# Sheet1.net
KiCad netlist of a schematic drawn in Altium Designer
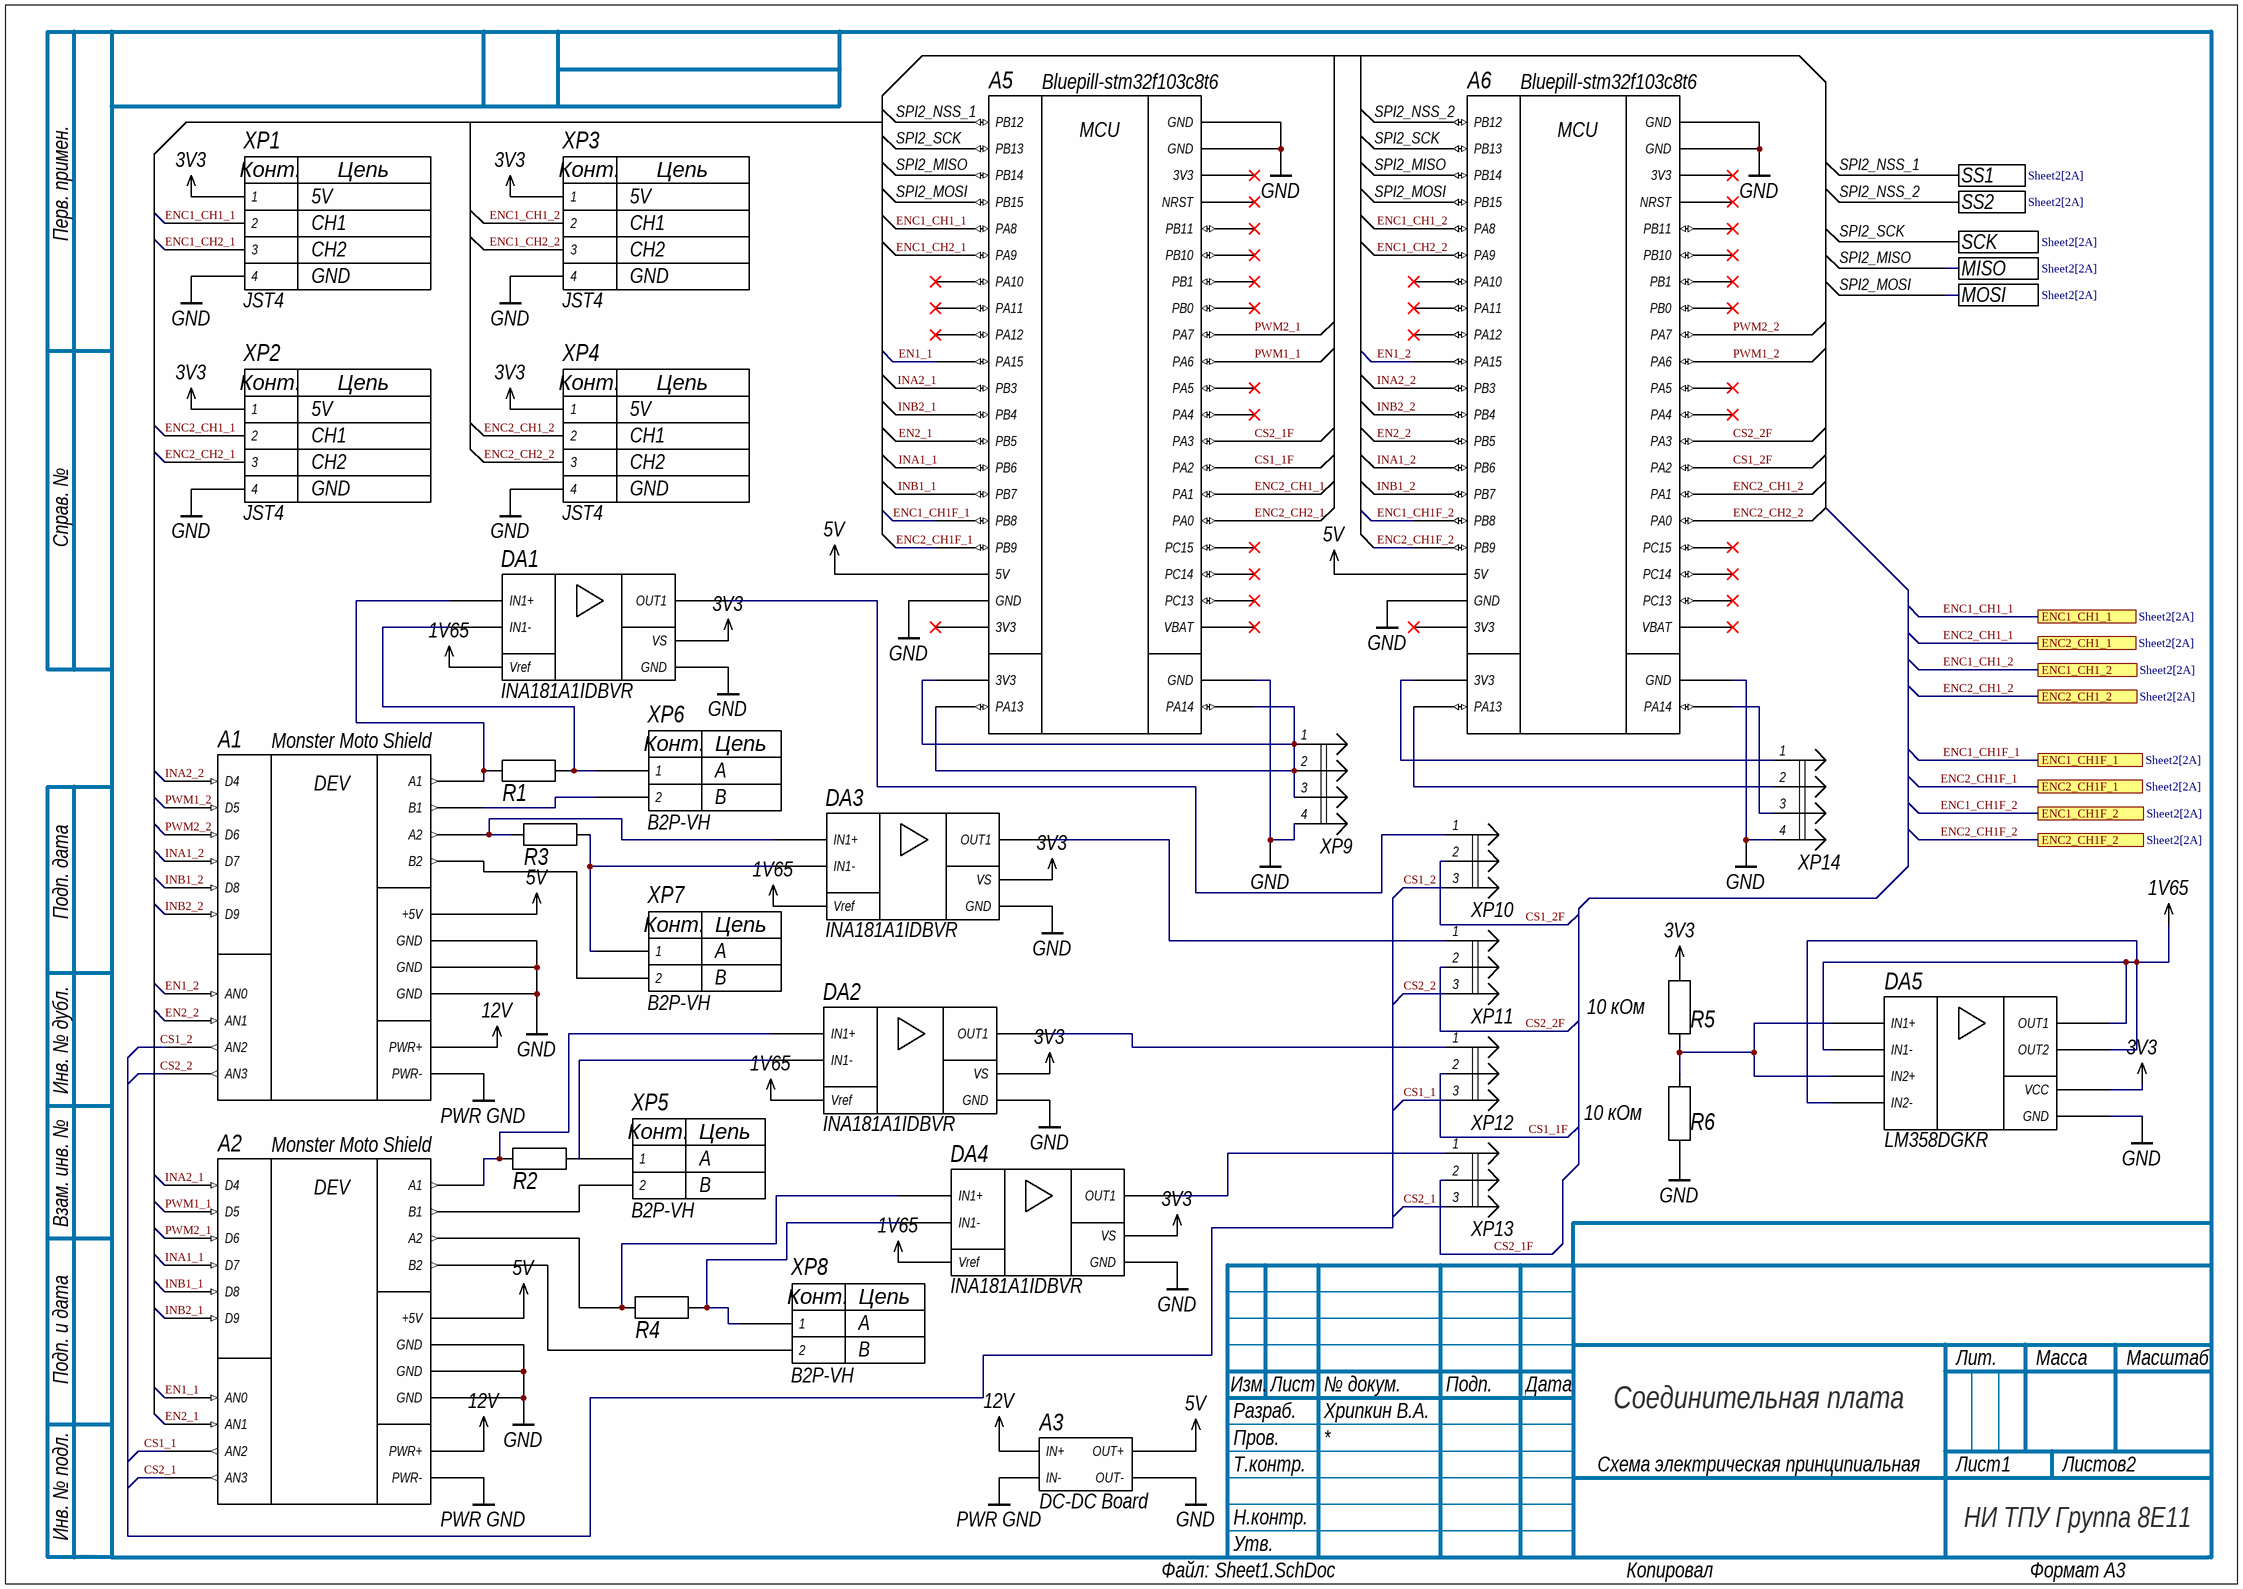
[diagram p0: Sheet1.SchDoc]

(export (version "E")
  (design (tool "Eeschema 10.0.6"))
  (components
    (comp (ref "A1")
      (value "Monster Moto Shield")
      (footprint "Monster Moto Shield")
      (libsource (lib "Schlib1") (part "MonsterMotoShield"))
    )
    (comp (ref "A2")
      (value "Monster Moto Shield")
      (footprint "Monster Moto Shield")
      (libsource (lib "Schlib1") (part "MonsterMotoShield"))
    )
    (comp (ref "A3")
      (value "DC-DC Board")
      (footprint "DC-DC Board")
      (description "Преобразователь напряжений 12-5В")
      (libsource (lib "Schlib1") (part "DC-DC"))
    )
    (comp (ref "A5")
      (value "Bluepill-stm32f103c8t6")
      (footprint "BluePill")
      (description "Отладочная плата на основе микроконтроллера stm32f103c8t6")
      (libsource (lib "Schlib1") (part "BluePill"))
    )
    (comp (ref "A6")
      (value "Bluepill-stm32f103c8t6")
      (footprint "BluePill")
      (description "Отладочная плата на основе микроконтроллера stm32f103c8t6")
      (libsource (lib "Schlib1") (part "BluePill"))
    )
    (comp (ref "DA1")
      (value "INA181A1IDBVR")
      (footprint "SOT236")
      (description "Усилители операционные, дифференциальные, инструментальные, Gain 20, SOT236")
      (libsource (lib "Schlib1") (part "INA181A1IDBVR"))
    )
    (comp (ref "DA2")
      (value "INA181A1IDBVR")
      (footprint "SOT236")
      (description "Усилители операционные, дифференциальные, инструментальные, Gain 20, SOT236")
      (libsource (lib "Schlib1") (part "INA181A1IDBVR"))
    )
    (comp (ref "DA3")
      (value "INA181A1IDBVR")
      (footprint "SOT236")
      (description "Усилители операционные, дифференциальные, инструментальные, Gain 20, SOT236")
      (libsource (lib "Schlib1") (part "INA181A1IDBVR"))
    )
    (comp (ref "DA4")
      (value "INA181A1IDBVR")
      (footprint "SOT236")
      (description "Усилители операционные, дифференциальные, инструментальные, Gain 20, SOT236")
      (libsource (lib "Schlib1") (part "INA181A1IDBVR"))
    )
    (comp (ref "DA5")
      (value "LM358DGKR")
      (footprint "VSSOP-8")
      (description "Операционный усилитель, Двойной, 700 кГц, 0.3 В/мкс, 3В до 32В, ± 1.5В до ± 16В, [VSSOP-8]")
      (libsource (lib "Schlib1") (part "LM358DGKR"))
    )
    (comp (ref "R1")
      (value "ва")
      (footprint "R1210")
      (description "Резистор постоянный")
      (libsource (lib "Schlib1") (part "Resisitor"))
    )
    (comp (ref "R2")
      (value "ва")
      (footprint "R1210")
      (description "Резистор постоянный")
      (libsource (lib "Schlib1") (part "Resisitor"))
    )
    (comp (ref "R3")
      (value "ва")
      (footprint "R1210")
      (description "Резистор постоянный")
      (libsource (lib "Schlib1") (part "Resisitor"))
    )
    (comp (ref "R4")
      (value "ва")
      (footprint "R1210")
      (description "Резистор постоянный")
      (libsource (lib "Schlib1") (part "Resisitor"))
    )
    (comp (ref "R5")
      (value "ва")
      (footprint "R0603")
      (description "Резистор постоянный")
      (libsource (lib "Schlib1") (part "R1_POSTOYANNYJ_W0.5"))
    )
    (comp (ref "R6")
      (value "ва")
      (footprint "R0603")
      (description "Резистор постоянный")
      (libsource (lib "Schlib1") (part "R1_POSTOYANNYJ_W0.5"))
    )
    (comp (ref "XP1") (value "JST4") (footprint "JST 4pin") (libsource (lib "Schlib1") (part "JST4")))
    (comp (ref "XP2") (value "JST4") (footprint "JST 4pin") (libsource (lib "Schlib1") (part "JST4")))
    (comp (ref "XP3") (value "JST4") (footprint "JST 4pin") (libsource (lib "Schlib1") (part "JST4")))
    (comp (ref "XP4") (value "JST4") (footprint "JST 4pin") (libsource (lib "Schlib1") (part "JST4")))
    (comp (ref "XP5")
      (value "B2P-VH")
      (footprint "B2P-VH")
      (description "JST VH(B2P-VH)")
      (libsource (lib "Schlib1") (part "JST VH(B2P-VH)"))
    )
    (comp (ref "XP6")
      (value "B2P-VH")
      (footprint "B2P-VH")
      (description "JST VH(B2P-VH)")
      (libsource (lib "Schlib1") (part "JST VH(B2P-VH)"))
    )
    (comp (ref "XP7")
      (value "B2P-VH")
      (footprint "B2P-VH")
      (description "JST VH(B2P-VH)")
      (libsource (lib "Schlib1") (part "JST VH(B2P-VH)"))
    )
    (comp (ref "XP8")
      (value "B2P-VH")
      (footprint "B2P-VH")
      (description "JST VH(B2P-VH)")
      (libsource (lib "Schlib1") (part "JST VH(B2P-VH)"))
    )
    (comp (ref "XP9")
      (value "~")
      (footprint "PLS-4")
      (description "PLS4")
      (libsource (lib "Schlib1") (part "Connector-4"))
    )
    (comp (ref "XP10")
      (value "~")
      (footprint "PLS-3")
      (description "PLS3")
      (libsource (lib "Schlib1") (part "Connector-3"))
    )
    (comp (ref "XP11")
      (value "~")
      (footprint "PLS-3")
      (description "PLS3")
      (libsource (lib "Schlib1") (part "Connector-3"))
    )
    (comp (ref "XP12")
      (value "~")
      (footprint "PLS-3")
      (description "PLS3")
      (libsource (lib "Schlib1") (part "Connector-3"))
    )
    (comp (ref "XP13")
      (value "~")
      (footprint "PLS-3")
      (description "PLS3")
      (libsource (lib "Schlib1") (part "Connector-3"))
    )
    (comp (ref "XP14")
      (value "~")
      (footprint "PLS-4")
      (description "PLS4")
      (libsource (lib "Schlib1") (part "Connector-4"))
    )
  )
  (nets
    (net (code "1") (name "/CS1_1") (class "Default")
      (node (ref "A2") (pin "3") (pinfunction "AN2_3") (pintype "output"))
      (node (ref "XP12") (pin "3") (pinfunction "3_3") (pintype "passive"))
    )
    (net (code "2") (name "/CS1_1F") (class "Default")
      (node (ref "A5") (pin "34") (pinfunction "PA2_34") (pintype "bidirectional"))
      (node (ref "XP12") (pin "2") (pinfunction "2_2") (pintype "passive"))
    )
    (net (code "3") (name "/CS1_2") (class "Default")
      (node (ref "A1") (pin "3") (pinfunction "AN2_3") (pintype "output"))
      (node (ref "XP10") (pin "3") (pinfunction "3_3") (pintype "passive"))
    )
    (net (code "4") (name "/CS1_2F") (class "Default")
      (node (ref "A6") (pin "34") (pinfunction "PA2_34") (pintype "bidirectional"))
      (node (ref "XP10") (pin "2") (pinfunction "2_2") (pintype "passive"))
    )
    (net (code "5") (name "/CS2_1") (class "Default")
      (node (ref "A2") (pin "4") (pinfunction "AN3_4") (pintype "output"))
      (node (ref "XP13") (pin "3") (pinfunction "3_3") (pintype "passive"))
    )
    (net (code "6") (name "/CS2_1F") (class "Default")
      (node (ref "A5") (pin "33") (pinfunction "PA3_33") (pintype "bidirectional"))
      (node (ref "XP13") (pin "2") (pinfunction "2_2") (pintype "passive"))
    )
    (net (code "7") (name "/CS2_2") (class "Default")
      (node (ref "A1") (pin "4") (pinfunction "AN3_4") (pintype "output"))
      (node (ref "XP11") (pin "3") (pinfunction "3_3") (pintype "passive"))
    )
    (net (code "8") (name "/CS2_2F") (class "Default")
      (node (ref "A6") (pin "33") (pinfunction "PA3_33") (pintype "bidirectional"))
      (node (ref "XP11") (pin "2") (pinfunction "2_2") (pintype "passive"))
    )
    (net (code "9") (name "/EN1_1") (class "Default")
      (node (ref "A2") (pin "1") (pinfunction "AN0_1") (pintype "input"))
      (node (ref "A5") (pin "10") (pinfunction "PA15_10") (pintype "bidirectional"))
    )
    (net (code "10") (name "/EN1_2") (class "Default")
      (node (ref "A1") (pin "1") (pinfunction "AN0_1") (pintype "input"))
      (node (ref "A6") (pin "10") (pinfunction "PA15_10") (pintype "bidirectional"))
    )
    (net (code "11") (name "/EN2_1") (class "Default")
      (node (ref "A2") (pin "2") (pinfunction "AN1_2") (pintype "input"))
      (node (ref "A5") (pin "13") (pinfunction "PB5_13") (pintype "bidirectional"))
    )
    (net (code "12") (name "/EN2_2") (class "Default")
      (node (ref "A1") (pin "2") (pinfunction "AN1_2") (pintype "input"))
      (node (ref "A6") (pin "13") (pinfunction "PB5_13") (pintype "bidirectional"))
    )
    (net (code "13") (name "/ENC1_CH1F_1") (class "Default")
      (node (ref "A5") (pin "16") (pinfunction "PB8_16") (pintype "bidirectional"))
    )
    (net (code "14") (name "/ENC1_CH1F_2") (class "Default")
      (node (ref "A6") (pin "16") (pinfunction "PB8_16") (pintype "bidirectional"))
    )
    (net (code "15") (name "/ENC1_CH1_1") (class "Default")
      (node (ref "A5") (pin "5") (pinfunction "PA8_5") (pintype "bidirectional"))
      (node (ref "XP1") (pin "2") (pinfunction "2_2") (pintype "passive"))
    )
    (net (code "16") (name "/ENC1_CH1_2") (class "Default")
      (node (ref "A6") (pin "5") (pinfunction "PA8_5") (pintype "bidirectional"))
      (node (ref "XP3") (pin "2") (pinfunction "2_2") (pintype "passive"))
    )
    (net (code "17") (name "/ENC1_CH2_1") (class "Default")
      (node (ref "A5") (pin "6") (pinfunction "PA9_6") (pintype "bidirectional"))
      (node (ref "XP1") (pin "3") (pinfunction "3_3") (pintype "passive"))
    )
    (net (code "18") (name "/ENC1_CH2_2") (class "Default")
      (node (ref "A6") (pin "6") (pinfunction "PA9_6") (pintype "bidirectional"))
      (node (ref "XP3") (pin "3") (pinfunction "3_3") (pintype "passive"))
    )
    (net (code "19") (name "/ENC2_CH1F_1") (class "Default")
      (node (ref "A5") (pin "17") (pinfunction "PB9_17") (pintype "bidirectional"))
    )
    (net (code "20") (name "/ENC2_CH1F_2") (class "Default")
      (node (ref "A6") (pin "17") (pinfunction "PB9_17") (pintype "bidirectional"))
    )
    (net (code "21") (name "/ENC2_CH1_1") (class "Default")
      (node (ref "A5") (pin "35") (pinfunction "PA1_35") (pintype "bidirectional"))
      (node (ref "XP2") (pin "2") (pinfunction "2_2") (pintype "passive"))
    )
    (net (code "22") (name "/ENC2_CH1_2") (class "Default")
      (node (ref "A6") (pin "35") (pinfunction "PA1_35") (pintype "bidirectional"))
      (node (ref "XP4") (pin "2") (pinfunction "2_2") (pintype "passive"))
    )
    (net (code "23") (name "/ENC2_CH2_1") (class "Default")
      (node (ref "A5") (pin "36") (pinfunction "PA0_36") (pintype "bidirectional"))
      (node (ref "XP2") (pin "3") (pinfunction "3_3") (pintype "passive"))
    )
    (net (code "24") (name "/ENC2_CH2_2") (class "Default")
      (node (ref "A6") (pin "36") (pinfunction "PA0_36") (pintype "bidirectional"))
      (node (ref "XP4") (pin "3") (pinfunction "3_3") (pintype "passive"))
    )
    (net (code "25") (name "/INA1_1") (class "Default")
      (node (ref "A2") (pin "8") (pinfunction "D7_8") (pintype "input"))
      (node (ref "A5") (pin "14") (pinfunction "PB6_14") (pintype "bidirectional"))
    )
    (net (code "26") (name "/INA1_2") (class "Default")
      (node (ref "A1") (pin "8") (pinfunction "D7_8") (pintype "input"))
      (node (ref "A6") (pin "14") (pinfunction "PB6_14") (pintype "bidirectional"))
    )
    (net (code "27") (name "/INA2_1") (class "Default")
      (node (ref "A2") (pin "5") (pinfunction "D4_5") (pintype "input"))
      (node (ref "A5") (pin "11") (pinfunction "PB3_11") (pintype "bidirectional"))
    )
    (net (code "28") (name "/INA2_2") (class "Default")
      (node (ref "A1") (pin "5") (pinfunction "D4_5") (pintype "input"))
      (node (ref "A6") (pin "11") (pinfunction "PB3_11") (pintype "bidirectional"))
    )
    (net (code "29") (name "/INB1_1") (class "Default")
      (node (ref "A2") (pin "9") (pinfunction "D8_9") (pintype "input"))
      (node (ref "A5") (pin "15") (pinfunction "PB7_15") (pintype "bidirectional"))
    )
    (net (code "30") (name "/INB1_2") (class "Default")
      (node (ref "A1") (pin "9") (pinfunction "D8_9") (pintype "input"))
      (node (ref "A6") (pin "15") (pinfunction "PB7_15") (pintype "bidirectional"))
    )
    (net (code "31") (name "/INB2_1") (class "Default")
      (node (ref "A2") (pin "10") (pinfunction "D9_10") (pintype "input"))
      (node (ref "A5") (pin "12") (pinfunction "PB4_12") (pintype "bidirectional"))
    )
    (net (code "32") (name "/INB2_2") (class "Default")
      (node (ref "A1") (pin "10") (pinfunction "D9_10") (pintype "input"))
      (node (ref "A6") (pin "12") (pinfunction "PB4_12") (pintype "bidirectional"))
    )
    (net (code "33") (name "/PWM1_1") (class "Default")
      (node (ref "A2") (pin "6") (pinfunction "D5_6") (pintype "input"))
      (node (ref "A5") (pin "30") (pinfunction "PA6_30") (pintype "bidirectional"))
    )
    (net (code "34") (name "/PWM1_2") (class "Default")
      (node (ref "A1") (pin "6") (pinfunction "D5_6") (pintype "input"))
      (node (ref "A6") (pin "30") (pinfunction "PA6_30") (pintype "bidirectional"))
    )
    (net (code "35") (name "/PWM2_1") (class "Default")
      (node (ref "A2") (pin "7") (pinfunction "D6_7") (pintype "input"))
      (node (ref "A5") (pin "29") (pinfunction "PA7_29") (pintype "bidirectional"))
    )
    (net (code "36") (name "/PWM2_2") (class "Default")
      (node (ref "A1") (pin "7") (pinfunction "D6_7") (pintype "input"))
      (node (ref "A6") (pin "29") (pinfunction "PA7_29") (pintype "bidirectional"))
    )
    (net (code "37") (name "/SPI2_MISO") (class "Default")
      (node (ref "A5") (pin "3") (pinfunction "PB14_3") (pintype "bidirectional"))
      (node (ref "A6") (pin "3") (pinfunction "PB14_3") (pintype "bidirectional"))
    )
    (net (code "38") (name "/SPI2_MOSI") (class "Default")
      (node (ref "A5") (pin "4") (pinfunction "PB15_4") (pintype "bidirectional"))
      (node (ref "A6") (pin "4") (pinfunction "PB15_4") (pintype "bidirectional"))
    )
    (net (code "39") (name "/SPI2_NSS_1") (class "Default")
      (node (ref "A5") (pin "1") (pinfunction "PB12_1") (pintype "bidirectional"))
    )
    (net (code "40") (name "/SPI2_NSS_2") (class "Default")
      (node (ref "A6") (pin "1") (pinfunction "PB12_1") (pintype "bidirectional"))
    )
    (net (code "41") (name "/SPI2_SCK") (class "Default")
      (node (ref "A5") (pin "2") (pinfunction "PB13_2") (pintype "bidirectional"))
      (node (ref "A6") (pin "2") (pinfunction "PB13_2") (pintype "bidirectional"))
    )
    (net (code "42") (name "1V65") (class "Default")
      (node (ref "DA1") (pin "1") (pinfunction "Vref_1") (pintype "passive"))
      (node (ref "DA2") (pin "1") (pinfunction "Vref_1") (pintype "passive"))
      (node (ref "DA3") (pin "1") (pinfunction "Vref_1") (pintype "passive"))
      (node (ref "DA4") (pin "1") (pinfunction "Vref_1") (pintype "passive"))
      (node (ref "DA5") (pin "1") (pinfunction "OUT1_1") (pintype "passive"))
      (node (ref "DA5") (pin "2") (pinfunction "IN1-_2") (pintype "passive"))
      (node (ref "DA5") (pin "6") (pinfunction "IN2-_6") (pintype "passive"))
      (node (ref "DA5") (pin "7") (pinfunction "OUT2_7") (pintype "passive"))
    )
    (net (code "43") (name "3V3") (class "Default")
      (node (ref "DA1") (pin "3") (pinfunction "VS_3") (pintype "passive"))
      (node (ref "DA2") (pin "3") (pinfunction "VS_3") (pintype "passive"))
      (node (ref "DA3") (pin "3") (pinfunction "VS_3") (pintype "passive"))
      (node (ref "DA4") (pin "3") (pinfunction "VS_3") (pintype "passive"))
      (node (ref "DA5") (pin "8") (pinfunction "VCC_8") (pintype "passive"))
      (node (ref "R5") (pin "2") (pinfunction "2_2") (pintype "passive"))
      (node (ref "XP1") (pin "1") (pinfunction "1_1") (pintype "passive"))
      (node (ref "XP2") (pin "1") (pinfunction "1_1") (pintype "passive"))
      (node (ref "XP3") (pin "1") (pinfunction "1_1") (pintype "passive"))
      (node (ref "XP4") (pin "1") (pinfunction "1_1") (pintype "passive"))
    )
    (net (code "44") (name "5V") (class "Default")
      (node (ref "A1") (pin "19") (pinfunction "+5V_19") (pintype "power_in"))
      (node (ref "A2") (pin "19") (pinfunction "+5V_19") (pintype "power_in"))
      (node (ref "A3") (pin "3") (pinfunction "OUT+_3") (pintype "passive"))
      (node (ref "A5") (pin "18") (pinfunction "5V_18") (pintype "power_in"))
      (node (ref "A6") (pin "18") (pinfunction "5V_18") (pintype "power_in"))
    )
    (net (code "45") (name "12V") (class "Default")
      (node (ref "A1") (pin "20") (pinfunction "PWR+_20") (pintype "power_in"))
      (node (ref "A2") (pin "20") (pinfunction "PWR+_20") (pintype "power_in"))
      (node (ref "A3") (pin "1") (pinfunction "IN+_1") (pintype "passive"))
    )
    (net (code "46") (name "GND") (class "Default")
      (node (ref "A1") (pin "16") (pinfunction "GND_16") (pintype "power_in"))
      (node (ref "A1") (pin "17") (pinfunction "GND_17") (pintype "power_in"))
      (node (ref "A1") (pin "18") (pinfunction "GND_18") (pintype "power_in"))
      (node (ref "A2") (pin "16") (pinfunction "GND_16") (pintype "power_in"))
      (node (ref "A2") (pin "17") (pinfunction "GND_17") (pintype "power_in"))
      (node (ref "A2") (pin "18") (pinfunction "GND_18") (pintype "power_in"))
      (node (ref "A3") (pin "4") (pinfunction "OUT-_4") (pintype "passive"))
      (node (ref "A5") (pin "19") (pinfunction "GND_19") (pintype "power_in"))
      (node (ref "A5") (pin "21") (pinfunction "GND_21") (pintype "power_in"))
      (node (ref "A5") (pin "22") (pinfunction "GND_22") (pintype "power_in"))
      (node (ref "A5") (pin "44") (pinfunction "GND_44") (pintype "power_in"))
      (node (ref "A6") (pin "19") (pinfunction "GND_19") (pintype "power_in"))
      (node (ref "A6") (pin "21") (pinfunction "GND_21") (pintype "power_in"))
      (node (ref "A6") (pin "22") (pinfunction "GND_22") (pintype "power_in"))
      (node (ref "A6") (pin "44") (pinfunction "GND_44") (pintype "power_in"))
      (node (ref "DA1") (pin "2") (pinfunction "GND_2") (pintype "power_in"))
      (node (ref "DA2") (pin "2") (pinfunction "GND_2") (pintype "power_in"))
      (node (ref "DA3") (pin "2") (pinfunction "GND_2") (pintype "power_in"))
      (node (ref "DA4") (pin "2") (pinfunction "GND_2") (pintype "power_in"))
      (node (ref "DA5") (pin "4") (pinfunction "GND_4") (pintype "power_in"))
      (node (ref "R6") (pin "1") (pinfunction "1_1") (pintype "passive"))
      (node (ref "XP1") (pin "4") (pinfunction "4_4") (pintype "passive"))
      (node (ref "XP14") (pin "4") (pinfunction "4_4") (pintype "passive"))
      (node (ref "XP2") (pin "4") (pinfunction "4_4") (pintype "passive"))
      (node (ref "XP3") (pin "4") (pinfunction "4_4") (pintype "passive"))
      (node (ref "XP4") (pin "4") (pinfunction "4_4") (pintype "passive"))
      (node (ref "XP9") (pin "4") (pinfunction "4_4") (pintype "passive"))
    )
    (net (code "47") (name "Net-(A1-A1)") (class "Default")
      (node (ref "A1") (pin "11") (pinfunction "A1_11") (pintype "output"))
      (node (ref "DA1") (pin "4") (pinfunction "IN1+_4") (pintype "passive"))
      (node (ref "R1") (pin "2") (pinfunction "2_2") (pintype "passive"))
    )
    (net (code "48") (name "Net-(A1-A2)") (class "Default")
      (node (ref "A1") (pin "13") (pinfunction "A2_13") (pintype "output"))
      (node (ref "DA3") (pin "4") (pinfunction "IN1+_4") (pintype "passive"))
      (node (ref "R3") (pin "2") (pinfunction "2_2") (pintype "passive"))
    )
    (net (code "49") (name "Net-(A1-B1)") (class "Default")
      (node (ref "A1") (pin "12") (pinfunction "B1_12") (pintype "output"))
      (node (ref "XP6") (pin "2") (pinfunction "2_2") (pintype "passive"))
    )
    (net (code "50") (name "Net-(A1-B2)") (class "Default")
      (node (ref "A1") (pin "14") (pinfunction "B2_14") (pintype "output"))
      (node (ref "XP7") (pin "2") (pinfunction "2_2") (pintype "passive"))
    )
    (net (code "51") (name "Net-(A2-A1)") (class "Default")
      (node (ref "A2") (pin "11") (pinfunction "A1_11") (pintype "output"))
      (node (ref "DA2") (pin "4") (pinfunction "IN1+_4") (pintype "passive"))
      (node (ref "R2") (pin "2") (pinfunction "2_2") (pintype "passive"))
    )
    (net (code "52") (name "Net-(A2-A2)") (class "Default")
      (node (ref "A2") (pin "13") (pinfunction "A2_13") (pintype "output"))
      (node (ref "DA4") (pin "4") (pinfunction "IN1+_4") (pintype "passive"))
      (node (ref "R4") (pin "2") (pinfunction "2_2") (pintype "passive"))
    )
    (net (code "53") (name "Net-(A2-B1)") (class "Default")
      (node (ref "A2") (pin "12") (pinfunction "B1_12") (pintype "output"))
      (node (ref "XP5") (pin "2") (pinfunction "2_2") (pintype "passive"))
    )
    (net (code "54") (name "Net-(A2-B2)") (class "Default")
      (node (ref "A2") (pin "14") (pinfunction "B2_14") (pintype "output"))
      (node (ref "XP8") (pin "2") (pinfunction "2_2") (pintype "passive"))
    )
    (net (code "55") (name "Net-(A5-PA13)") (class "Default")
      (node (ref "A5") (pin "41") (pinfunction "3V3_41") (pintype "power_in"))
      (node (ref "A5") (pin "42") (pinfunction "PA13_42") (pintype "bidirectional"))
      (node (ref "A5") (pin "43") (pinfunction "PA14_43") (pintype "bidirectional"))
      (node (ref "XP9") (pin "1") (pinfunction "1_1") (pintype "passive"))
      (node (ref "XP9") (pin "2") (pinfunction "2_2") (pintype "passive"))
      (node (ref "XP9") (pin "3") (pinfunction "3_3") (pintype "passive"))
    )
    (net (code "56") (name "Net-(A6-3V3-Pad41)") (class "Default")
      (node (ref "A6") (pin "41") (pinfunction "3V3_41") (pintype "power_in"))
      (node (ref "XP14") (pin "1") (pinfunction "1_1") (pintype "passive"))
    )
    (net (code "57") (name "Net-(A6-PA13)") (class "Default")
      (node (ref "A6") (pin "42") (pinfunction "PA13_42") (pintype "bidirectional"))
      (node (ref "XP14") (pin "2") (pinfunction "2_2") (pintype "passive"))
    )
    (net (code "58") (name "Net-(A6-PA14)") (class "Default")
      (node (ref "A6") (pin "43") (pinfunction "PA14_43") (pintype "bidirectional"))
      (node (ref "XP14") (pin "3") (pinfunction "3_3") (pintype "passive"))
    )
    (net (code "59") (name "Net-(DA1-IN1-)") (class "Default")
      (node (ref "DA1") (pin "5") (pinfunction "IN1-_5") (pintype "passive"))
      (node (ref "R1") (pin "1") (pinfunction "1_1") (pintype "passive"))
      (node (ref "XP6") (pin "1") (pinfunction "1_1") (pintype "passive"))
    )
    (net (code "60") (name "Net-(DA1-OUT1)") (class "Default")
      (node (ref "DA1") (pin "6") (pinfunction "OUT1_6") (pintype "passive"))
      (node (ref "XP10") (pin "1") (pinfunction "1_1") (pintype "passive"))
    )
    (net (code "61") (name "Net-(DA2-IN1-)") (class "Default")
      (node (ref "DA2") (pin "5") (pinfunction "IN1-_5") (pintype "passive"))
      (node (ref "R2") (pin "1") (pinfunction "1_1") (pintype "passive"))
      (node (ref "XP5") (pin "1") (pinfunction "1_1") (pintype "passive"))
    )
    (net (code "62") (name "Net-(DA2-OUT1)") (class "Default")
      (node (ref "DA2") (pin "6") (pinfunction "OUT1_6") (pintype "passive"))
      (node (ref "XP12") (pin "1") (pinfunction "1_1") (pintype "passive"))
    )
    (net (code "63") (name "Net-(DA3-IN1-)") (class "Default")
      (node (ref "DA3") (pin "5") (pinfunction "IN1-_5") (pintype "passive"))
      (node (ref "R3") (pin "1") (pinfunction "1_1") (pintype "passive"))
      (node (ref "XP7") (pin "1") (pinfunction "1_1") (pintype "passive"))
    )
    (net (code "64") (name "Net-(DA3-OUT1)") (class "Default")
      (node (ref "DA3") (pin "6") (pinfunction "OUT1_6") (pintype "passive"))
      (node (ref "XP11") (pin "1") (pinfunction "1_1") (pintype "passive"))
    )
    (net (code "65") (name "Net-(DA4-IN1-)") (class "Default")
      (node (ref "DA4") (pin "5") (pinfunction "IN1-_5") (pintype "passive"))
      (node (ref "R4") (pin "1") (pinfunction "1_1") (pintype "passive"))
      (node (ref "XP8") (pin "1") (pinfunction "1_1") (pintype "passive"))
    )
    (net (code "66") (name "Net-(DA4-OUT1)") (class "Default")
      (node (ref "DA4") (pin "6") (pinfunction "OUT1_6") (pintype "passive"))
      (node (ref "XP13") (pin "1") (pinfunction "1_1") (pintype "passive"))
    )
    (net (code "67") (name "Net-(DA5-IN1+)") (class "Default")
      (node (ref "DA5") (pin "3") (pinfunction "IN1+_3") (pintype "passive"))
      (node (ref "DA5") (pin "5") (pinfunction "IN2+_5") (pintype "passive"))
      (node (ref "R5") (pin "1") (pinfunction "1_1") (pintype "passive"))
      (node (ref "R6") (pin "2") (pinfunction "2_2") (pintype "passive"))
    )
    (net (code "68") (name "PWR GND") (class "Default")
      (node (ref "A1") (pin "21") (pinfunction "PWR-_21") (pintype "power_in"))
      (node (ref "A2") (pin "21") (pinfunction "PWR-_21") (pintype "power_in"))
      (node (ref "A3") (pin "2") (pinfunction "IN-_2") (pintype "passive"))
    )
    (net (code "69") (name "unconnected-(A5-3V3-Pad20)") (class "Default")
      (node (ref "A5") (pin "20") (pinfunction "3V3_20") (pintype "power_in+no_connect"))
    )
    (net (code "70") (name "unconnected-(A5-3V3-Pad23)") (class "Default")
      (node (ref "A5") (pin "23") (pinfunction "3V3_23") (pintype "power_in+no_connect"))
    )
    (net (code "71") (name "unconnected-(A5-NRST-Pad24)") (class "Default")
      (node (ref "A5") (pin "24") (pinfunction "NRST_24") (pintype "passive+no_connect"))
    )
    (net (code "72") (name "unconnected-(A5-PA4-Pad32)") (class "Default")
      (node (ref "A5") (pin "32") (pinfunction "PA4_32") (pintype "bidirectional+no_connect"))
    )
    (net (code "73") (name "unconnected-(A5-PA5-Pad31)") (class "Default")
      (node (ref "A5") (pin "31") (pinfunction "PA5_31") (pintype "bidirectional+no_connect"))
    )
    (net (code "74") (name "unconnected-(A5-PA10-Pad7)") (class "Default")
      (node (ref "A5") (pin "7") (pinfunction "PA10_7") (pintype "bidirectional+no_connect"))
    )
    (net (code "75") (name "unconnected-(A5-PA11-Pad8)") (class "Default")
      (node (ref "A5") (pin "8") (pinfunction "PA11_8") (pintype "bidirectional+no_connect"))
    )
    (net (code "76") (name "unconnected-(A5-PA12-Pad9)") (class "Default")
      (node (ref "A5") (pin "9") (pinfunction "PA12_9") (pintype "bidirectional+no_connect"))
    )
    (net (code "77") (name "unconnected-(A5-PB0-Pad28)") (class "Default")
      (node (ref "A5") (pin "28") (pinfunction "PB0_28") (pintype "bidirectional+no_connect"))
    )
    (net (code "78") (name "unconnected-(A5-PB1-Pad27)") (class "Default")
      (node (ref "A5") (pin "27") (pinfunction "PB1_27") (pintype "bidirectional+no_connect"))
    )
    (net (code "79") (name "unconnected-(A5-PB10-Pad26)") (class "Default")
      (node (ref "A5") (pin "26") (pinfunction "PB10_26") (pintype "bidirectional+no_connect"))
    )
    (net (code "80") (name "unconnected-(A5-PB11-Pad25)") (class "Default")
      (node (ref "A5") (pin "25") (pinfunction "PB11_25") (pintype "bidirectional+no_connect"))
    )
    (net (code "81") (name "unconnected-(A5-PC13-Pad39)") (class "Default")
      (node (ref "A5") (pin "39") (pinfunction "PC13_39") (pintype "bidirectional+no_connect"))
    )
    (net (code "82") (name "unconnected-(A5-PC14-Pad38)") (class "Default")
      (node (ref "A5") (pin "38") (pinfunction "PC14_38") (pintype "bidirectional+no_connect"))
    )
    (net (code "83") (name "unconnected-(A5-PC15-Pad37)") (class "Default")
      (node (ref "A5") (pin "37") (pinfunction "PC15_37") (pintype "bidirectional+no_connect"))
    )
    (net (code "84") (name "unconnected-(A5-VBAT-Pad40)") (class "Default")
      (node (ref "A5") (pin "40") (pinfunction "VBAT_40") (pintype "power_in+no_connect"))
    )
    (net (code "85") (name "unconnected-(A6-3V3-Pad20)") (class "Default")
      (node (ref "A6") (pin "20") (pinfunction "3V3_20") (pintype "power_in+no_connect"))
    )
    (net (code "86") (name "unconnected-(A6-3V3-Pad23)") (class "Default")
      (node (ref "A6") (pin "23") (pinfunction "3V3_23") (pintype "power_in+no_connect"))
    )
    (net (code "87") (name "unconnected-(A6-NRST-Pad24)") (class "Default")
      (node (ref "A6") (pin "24") (pinfunction "NRST_24") (pintype "passive+no_connect"))
    )
    (net (code "88") (name "unconnected-(A6-PA4-Pad32)") (class "Default")
      (node (ref "A6") (pin "32") (pinfunction "PA4_32") (pintype "bidirectional+no_connect"))
    )
    (net (code "89") (name "unconnected-(A6-PA5-Pad31)") (class "Default")
      (node (ref "A6") (pin "31") (pinfunction "PA5_31") (pintype "bidirectional+no_connect"))
    )
    (net (code "90") (name "unconnected-(A6-PA10-Pad7)") (class "Default")
      (node (ref "A6") (pin "7") (pinfunction "PA10_7") (pintype "bidirectional+no_connect"))
    )
    (net (code "91") (name "unconnected-(A6-PA11-Pad8)") (class "Default")
      (node (ref "A6") (pin "8") (pinfunction "PA11_8") (pintype "bidirectional+no_connect"))
    )
    (net (code "92") (name "unconnected-(A6-PA12-Pad9)") (class "Default")
      (node (ref "A6") (pin "9") (pinfunction "PA12_9") (pintype "bidirectional+no_connect"))
    )
    (net (code "93") (name "unconnected-(A6-PB0-Pad28)") (class "Default")
      (node (ref "A6") (pin "28") (pinfunction "PB0_28") (pintype "bidirectional+no_connect"))
    )
    (net (code "94") (name "unconnected-(A6-PB1-Pad27)") (class "Default")
      (node (ref "A6") (pin "27") (pinfunction "PB1_27") (pintype "bidirectional+no_connect"))
    )
    (net (code "95") (name "unconnected-(A6-PB10-Pad26)") (class "Default")
      (node (ref "A6") (pin "26") (pinfunction "PB10_26") (pintype "bidirectional+no_connect"))
    )
    (net (code "96") (name "unconnected-(A6-PB11-Pad25)") (class "Default")
      (node (ref "A6") (pin "25") (pinfunction "PB11_25") (pintype "bidirectional+no_connect"))
    )
    (net (code "97") (name "unconnected-(A6-PC13-Pad39)") (class "Default")
      (node (ref "A6") (pin "39") (pinfunction "PC13_39") (pintype "bidirectional+no_connect"))
    )
    (net (code "98") (name "unconnected-(A6-PC14-Pad38)") (class "Default")
      (node (ref "A6") (pin "38") (pinfunction "PC14_38") (pintype "bidirectional+no_connect"))
    )
    (net (code "99") (name "unconnected-(A6-PC15-Pad37)") (class "Default")
      (node (ref "A6") (pin "37") (pinfunction "PC15_37") (pintype "bidirectional+no_connect"))
    )
    (net (code "100") (name "unconnected-(A6-VBAT-Pad40)") (class "Default")
      (node (ref "A6") (pin "40") (pinfunction "VBAT_40") (pintype "power_in+no_connect"))
    )
  )
)
